# EnDat.net
KiCad netlist of a schematic drawn in Altium Designer
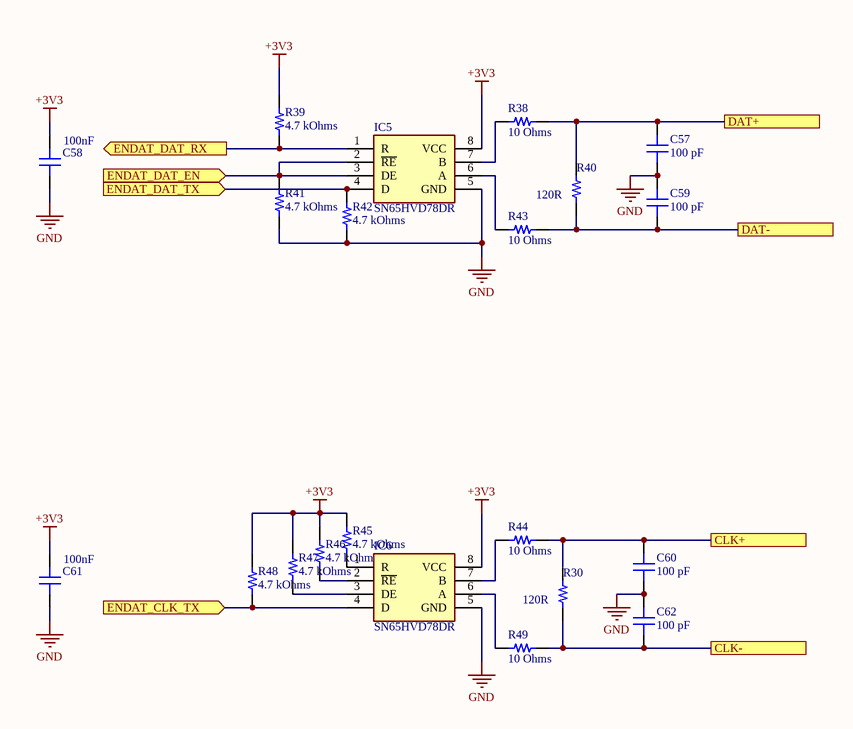
[diagram p0: EnDat.SchDoc]

(export (version "E")
  (design (tool "Eeschema 10.0.6"))
  (components
    (comp (ref "C57")
      (value "100 pF")
      (footprint "CAP 0402_1005")
      (description "CAP CER 100PF 50V C0G/NP0 0402")
      (fields
        (field (name "PART NUMBER") "500X07N101MV4T")
        (field (name "CAPACITANCE") "100 pF")
        (field (name "MANUFACTURER") "Johanson Dielectrics Inc.")
      )
      (libsource (lib "Celestial Altium Library - altium_library") (part "Capacitor"))
    )
    (comp (ref "C58")
      (value "100nF")
      (footprint "CAP 0402_1005")
      (description "CAP CER 1UF 16V X5R 0402")
      (fields (field (name "PART NUMBER") "C29266") (field (name "MANUFACTURER") "Samsung Electro-Mechanics"))
      (libsource (lib "Celestial Altium Library - altium_library") (part "Capacitor"))
    )
    (comp (ref "C59")
      (value "100 pF")
      (footprint "CAP 0402_1005")
      (description "CAP CER 100PF 50V C0G/NP0 0402")
      (fields
        (field (name "PART NUMBER") "500X07N101MV4T")
        (field (name "CAPACITANCE") "100 pF")
        (field (name "MANUFACTURER") "Johanson Dielectrics Inc.")
      )
      (libsource (lib "Celestial Altium Library - altium_library") (part "Capacitor"))
    )
    (comp (ref "C60")
      (value "100 pF")
      (footprint "CAP 0402_1005")
      (description "CAP CER 100PF 50V C0G/NP0 0402")
      (fields
        (field (name "PART NUMBER") "500X07N101MV4T")
        (field (name "CAPACITANCE") "100 pF")
        (field (name "MANUFACTURER") "Johanson Dielectrics Inc.")
      )
      (libsource (lib "Celestial Altium Library - altium_library") (part "Capacitor"))
    )
    (comp (ref "C61")
      (value "100nF")
      (footprint "CAP 0402_1005")
      (description "CAP CER 1UF 16V X5R 0402")
      (fields (field (name "PART NUMBER") "C29266") (field (name "MANUFACTURER") "Samsung Electro-Mechanics"))
      (libsource (lib "Celestial Altium Library - altium_library") (part "Capacitor"))
    )
    (comp (ref "C62")
      (value "100 pF")
      (footprint "CAP 0402_1005")
      (description "CAP CER 100PF 50V C0G/NP0 0402")
      (fields
        (field (name "PART NUMBER") "500X07N101MV4T")
        (field (name "CAPACITANCE") "100 pF")
        (field (name "MANUFACTURER") "Johanson Dielectrics Inc.")
      )
      (libsource (lib "Celestial Altium Library - altium_library") (part "Capacitor"))
    )
    (comp (ref "IC5")
      (value "SN65HVD78DR")
      (footprint "PcbLib1:SOIC127P600X175-8N")
      (description "Integrated Circuit")
      (fields (field (name "MOUSER PART NUMBER") "595-SN65HVD78DR"))
      (libsource (lib "*") (part "SN65HVD78DR"))
    )
    (comp (ref "IC6")
      (value "SN65HVD78DR")
      (footprint "PcbLib1:SOIC127P600X175-8N")
      (description "Integrated Circuit")
      (fields (field (name "MOUSER PART NUMBER") "595-SN65HVD78DR"))
      (libsource (lib "*") (part "SN65HVD78DR"))
    )
    (comp (ref "R30")
      (value "120R")
      (footprint "RES 0603_1608")
      (description "RESA-AS 0603 10R 1% 100MW TC100")
      (fields (field (name "PART NUMBER") "CR0603AFX-10R0EAS") (field (name "MANUFACTURER") "Bourns Inc."))
      (libsource (lib "Celestial Altium Library - altium_library") (part "Resistor"))
    )
    (comp (ref "R38")
      (value "10 Ohms")
      (footprint "RES 0402_1005")
      (description "RES 10 OHM 5% 1/16W 0402")
      (fields
        (field (name "PART NUMBER") "WR04X100 JTL")
        (field (name "MANUFACTURER") "Walsin Technology Corporation")
      )
      (libsource (lib "Celestial Altium Library - altium_library") (part "Resistor"))
    )
    (comp (ref "R39")
      (value "4.7 kOhms")
      (footprint "RES 0402_1005")
      (description "RES 4.7K OHM 1% 1/16W 0402")
      (fields
        (field (name "PART NUMBER") "WR04X4701FTL")
        (field (name "MANUFACTURER") "Walsin Technology Corporation")
      )
      (libsource (lib "Celestial Altium Library - altium_library") (part "Resistor"))
    )
    (comp (ref "R40")
      (value "120R")
      (footprint "RES 0603_1608")
      (description "RESA-AS 0603 10R 1% 100MW TC100")
      (fields (field (name "PART NUMBER") "CR0603AFX-10R0EAS") (field (name "MANUFACTURER") "Bourns Inc."))
      (libsource (lib "Celestial Altium Library - altium_library") (part "Resistor"))
    )
    (comp (ref "R41")
      (value "4.7 kOhms")
      (footprint "RES 0402_1005")
      (description "RES 4.7K OHM 1% 1/16W 0402")
      (fields
        (field (name "PART NUMBER") "WR04X4701FTL")
        (field (name "MANUFACTURER") "Walsin Technology Corporation")
      )
      (libsource (lib "Celestial Altium Library - altium_library") (part "Resistor"))
    )
    (comp (ref "R42")
      (value "4.7 kOhms")
      (footprint "RES 0402_1005")
      (description "RES 4.7K OHM 1% 1/16W 0402")
      (fields
        (field (name "PART NUMBER") "WR04X4701FTL")
        (field (name "MANUFACTURER") "Walsin Technology Corporation")
      )
      (libsource (lib "Celestial Altium Library - altium_library") (part "Resistor"))
    )
    (comp (ref "R43")
      (value "10 Ohms")
      (footprint "RES 0402_1005")
      (description "RES 10 OHM 5% 1/16W 0402")
      (fields
        (field (name "PART NUMBER") "WR04X100 JTL")
        (field (name "MANUFACTURER") "Walsin Technology Corporation")
      )
      (libsource (lib "Celestial Altium Library - altium_library") (part "Resistor"))
    )
    (comp (ref "R44")
      (value "10 Ohms")
      (footprint "RES 0402_1005")
      (description "RES 10 OHM 5% 1/16W 0402")
      (fields
        (field (name "PART NUMBER") "WR04X100 JTL")
        (field (name "MANUFACTURER") "Walsin Technology Corporation")
      )
      (libsource (lib "Celestial Altium Library - altium_library") (part "Resistor"))
    )
    (comp (ref "R45")
      (value "4.7 kOhms")
      (footprint "RES 0402_1005")
      (description "RES 4.7K OHM 1% 1/16W 0402")
      (fields
        (field (name "PART NUMBER") "WR04X4701FTL")
        (field (name "MANUFACTURER") "Walsin Technology Corporation")
      )
      (libsource (lib "Celestial Altium Library - altium_library") (part "Resistor"))
    )
    (comp (ref "R46")
      (value "4.7 kOhms")
      (footprint "RES 0402_1005")
      (description "RES 4.7K OHM 1% 1/16W 0402")
      (fields
        (field (name "PART NUMBER") "WR04X4701FTL")
        (field (name "MANUFACTURER") "Walsin Technology Corporation")
      )
      (libsource (lib "Celestial Altium Library - altium_library") (part "Resistor"))
    )
    (comp (ref "R47")
      (value "4.7 kOhms")
      (footprint "RES 0402_1005")
      (description "RES 4.7K OHM 1% 1/16W 0402")
      (fields
        (field (name "PART NUMBER") "WR04X4701FTL")
        (field (name "MANUFACTURER") "Walsin Technology Corporation")
      )
      (libsource (lib "Celestial Altium Library - altium_library") (part "Resistor"))
    )
    (comp (ref "R48")
      (value "4.7 kOhms")
      (footprint "RES 0402_1005")
      (description "RES 4.7K OHM 1% 1/16W 0402")
      (fields
        (field (name "PART NUMBER") "WR04X4701FTL")
        (field (name "MANUFACTURER") "Walsin Technology Corporation")
      )
      (libsource (lib "Celestial Altium Library - altium_library") (part "Resistor"))
    )
    (comp (ref "R49")
      (value "10 Ohms")
      (footprint "RES 0402_1005")
      (description "RES 10 OHM 5% 1/16W 0402")
      (fields
        (field (name "PART NUMBER") "WR04X100 JTL")
        (field (name "MANUFACTURER") "Walsin Technology Corporation")
      )
      (libsource (lib "Celestial Altium Library - altium_library") (part "Resistor"))
    )
  )
  (nets
    (net (code "1") (name "+3V3") (class "Default")
      (node (ref "C58") (pin "2") (pinfunction "2_2") (pintype "passive"))
      (node (ref "C61") (pin "2") (pinfunction "2_2") (pintype "passive"))
      (node (ref "IC5") (pin "8") (pinfunction "VCC_8") (pintype "passive"))
      (node (ref "IC6") (pin "8") (pinfunction "VCC_8") (pintype "passive"))
      (node (ref "R39") (pin "2") (pinfunction "2_2") (pintype "passive"))
      (node (ref "R45") (pin "2") (pinfunction "2_2") (pintype "passive"))
      (node (ref "R46") (pin "2") (pinfunction "2_2") (pintype "passive"))
      (node (ref "R47") (pin "2") (pinfunction "2_2") (pintype "passive"))
      (node (ref "R48") (pin "2") (pinfunction "2_2") (pintype "passive"))
    )
    (net (code "2") (name "/CLK+") (class "Default")
      (node (ref "C60") (pin "2") (pinfunction "2_2") (pintype "passive"))
      (node (ref "R30") (pin "2") (pinfunction "2_2") (pintype "passive"))
      (node (ref "R44") (pin "2") (pinfunction "2_2") (pintype "passive"))
    )
    (net (code "3") (name "/CLK-") (class "Default")
      (node (ref "C62") (pin "1") (pinfunction "1_1") (pintype "passive"))
      (node (ref "R30") (pin "1") (pinfunction "1_1") (pintype "passive"))
      (node (ref "R49") (pin "2") (pinfunction "2_2") (pintype "passive"))
    )
    (net (code "4") (name "/DAT+") (class "Default")
      (node (ref "C57") (pin "2") (pinfunction "2_2") (pintype "passive"))
      (node (ref "R38") (pin "2") (pinfunction "2_2") (pintype "passive"))
      (node (ref "R40") (pin "2") (pinfunction "2_2") (pintype "passive"))
    )
    (net (code "5") (name "/DAT-") (class "Default")
      (node (ref "C59") (pin "1") (pinfunction "1_1") (pintype "passive"))
      (node (ref "R40") (pin "1") (pinfunction "1_1") (pintype "passive"))
      (node (ref "R43") (pin "2") (pinfunction "2_2") (pintype "passive"))
    )
    (net (code "6") (name "/ENDAT_CLK_TX") (class "Default")
      (node (ref "IC6") (pin "4") (pinfunction "D_4") (pintype "passive"))
      (node (ref "R48") (pin "1") (pinfunction "1_1") (pintype "passive"))
    )
    (net (code "7") (name "/ENDAT_DAT_EN") (class "Default")
      (node (ref "IC5") (pin "2") (pinfunction "~{RE}_2") (pintype "passive"))
      (node (ref "IC5") (pin "3") (pinfunction "DE_3") (pintype "passive"))
      (node (ref "R41") (pin "2") (pinfunction "2_2") (pintype "passive"))
    )
    (net (code "8") (name "/ENDAT_DAT_RX") (class "Default")
      (node (ref "IC5") (pin "1") (pinfunction "R_1") (pintype "passive"))
      (node (ref "R39") (pin "1") (pinfunction "1_1") (pintype "passive"))
    )
    (net (code "9") (name "/ENDAT_DAT_TX") (class "Default")
      (node (ref "IC5") (pin "4") (pinfunction "D_4") (pintype "passive"))
      (node (ref "R42") (pin "2") (pinfunction "2_2") (pintype "passive"))
    )
    (net (code "10") (name "GND") (class "Default")
      (node (ref "C57") (pin "1") (pinfunction "1_1") (pintype "passive"))
      (node (ref "C58") (pin "1") (pinfunction "1_1") (pintype "passive"))
      (node (ref "C59") (pin "2") (pinfunction "2_2") (pintype "passive"))
      (node (ref "C60") (pin "1") (pinfunction "1_1") (pintype "passive"))
      (node (ref "C61") (pin "1") (pinfunction "1_1") (pintype "passive"))
      (node (ref "C62") (pin "2") (pinfunction "2_2") (pintype "passive"))
      (node (ref "IC5") (pin "5") (pinfunction "GND_5") (pintype "passive"))
      (node (ref "IC6") (pin "5") (pinfunction "GND_5") (pintype "passive"))
      (node (ref "R41") (pin "1") (pinfunction "1_1") (pintype "passive"))
      (node (ref "R42") (pin "1") (pinfunction "1_1") (pintype "passive"))
    )
    (net (code "11") (name "Net-(IC5-A)") (class "Default")
      (node (ref "IC5") (pin "6") (pinfunction "A_6") (pintype "passive"))
      (node (ref "R43") (pin "1") (pinfunction "1_1") (pintype "passive"))
    )
    (net (code "12") (name "Net-(IC5-B)") (class "Default")
      (node (ref "IC5") (pin "7") (pinfunction "B_7") (pintype "passive"))
      (node (ref "R38") (pin "1") (pinfunction "1_1") (pintype "passive"))
    )
    (net (code "13") (name "Net-(IC6-A)") (class "Default")
      (node (ref "IC6") (pin "6") (pinfunction "A_6") (pintype "passive"))
      (node (ref "R49") (pin "1") (pinfunction "1_1") (pintype "passive"))
    )
    (net (code "14") (name "Net-(IC6-B)") (class "Default")
      (node (ref "IC6") (pin "7") (pinfunction "B_7") (pintype "passive"))
      (node (ref "R44") (pin "1") (pinfunction "1_1") (pintype "passive"))
    )
    (net (code "15") (name "Net-(IC6-DE)") (class "Default")
      (node (ref "IC6") (pin "3") (pinfunction "DE_3") (pintype "passive"))
      (node (ref "R47") (pin "1") (pinfunction "1_1") (pintype "passive"))
    )
    (net (code "16") (name "Net-(IC6-R)") (class "Default")
      (node (ref "IC6") (pin "1") (pinfunction "R_1") (pintype "passive"))
      (node (ref "R45") (pin "1") (pinfunction "1_1") (pintype "passive"))
    )
    (net (code "17") (name "Net-(IC6-~{RE})") (class "Default")
      (node (ref "IC6") (pin "2") (pinfunction "~{RE}_2") (pintype "passive"))
      (node (ref "R46") (pin "1") (pinfunction "1_1") (pintype "passive"))
    )
  )
)
